# MD029A_DRV8300.net
KiCad netlist of a schematic drawn in Altium Designer
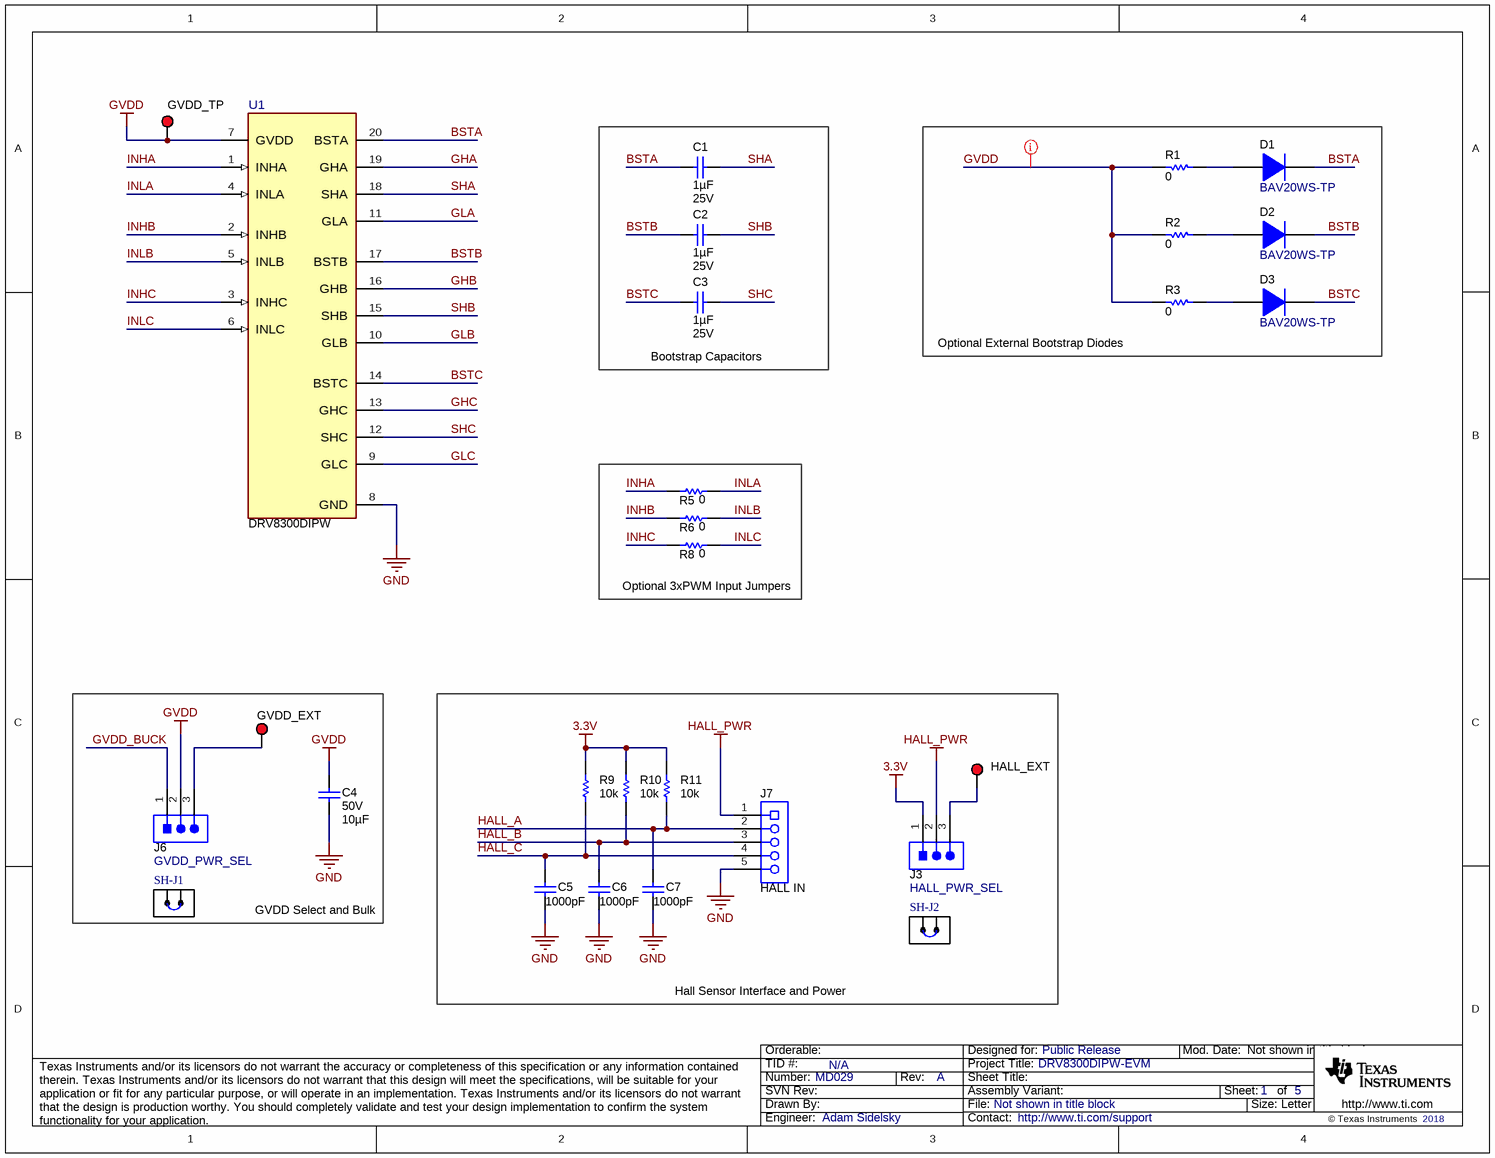
[diagram p0: MD029A_DRV8300.SchDoc]

(export (version "E")
  (design (tool "Eeschema 10.0.6"))
  (components
    (comp (ref "C1")
      (value "CL21B105KAFNNNE")
      (footprint "0805L")
      (description "CAP, CERM, 1 µF, 25 V,+/- 10%, X7R, 0805")
      (fields
        (field (name "MANUFACTURER") "Samsung Electro-Mechanics")
        (field (name "CAP_F") "1µF")
        (field (name "VDC_V") "25V")
      )
      (libsource (lib "Altium Vault - TI") (part "Capacitor"))
    )
    (comp (ref "C2")
      (value "CL21B105KAFNNNE")
      (footprint "0805L")
      (description "CAP, CERM, 1 µF, 25 V,+/- 10%, X7R, 0805")
      (fields
        (field (name "MANUFACTURER") "Samsung Electro-Mechanics")
        (field (name "CAP_F") "1µF")
        (field (name "VDC_V") "25V")
      )
      (libsource (lib "Altium Vault - TI") (part "Capacitor"))
    )
    (comp (ref "C3")
      (value "CL21B105KAFNNNE")
      (footprint "0805L")
      (description "CAP, CERM, 1 µF, 25 V,+/- 10%, X7R, 0805")
      (fields
        (field (name "MANUFACTURER") "Samsung Electro-Mechanics")
        (field (name "CAP_F") "1µF")
        (field (name "VDC_V") "25V")
      )
      (libsource (lib "Altium Vault - TI") (part "Capacitor"))
    )
    (comp (ref "C4")
      (value "CL32B106KBJNNWE")
      (footprint "1210_270L")
      (description "CAP, CERM, 10 µF, 50 V,+/- 10%, X7R, 1210")
      (fields
        (field (name "MANUFACTURER") "Samsung Electro-Mechanics")
        (field (name "VDC_V") "50V")
        (field (name "VALUEDISPLAYED") "10µF")
      )
      (libsource (lib "Altium Vault - TI") (part "Capacitor"))
    )
    (comp (ref "C5")
      (value "885012206034")
      (footprint "0603L")
      (description "CAP, CERM, 1000 pF, 16 V, +/- 10%, X7R, 0603")
      (fields
        (field (name "MANUFACTURER") "Wurth Elektronik")
        (field (name "VALUEDISPLAYED") "1000pF")
        (field (name "PUBLISHER") "Texas Instruments")
      )
      (libsource (lib "Altium Vault - TI") (part "CMP-0006826-4"))
    )
    (comp (ref "C6")
      (value "885012206034")
      (footprint "0603L")
      (description "CAP, CERM, 1000 pF, 16 V, +/- 10%, X7R, 0603")
      (fields
        (field (name "MANUFACTURER") "Wurth Elektronik")
        (field (name "VALUEDISPLAYED") "1000pF")
        (field (name "PUBLISHER") "Texas Instruments")
      )
      (libsource (lib "Altium Vault - TI") (part "CMP-0006826-4"))
    )
    (comp (ref "C7")
      (value "885012206034")
      (footprint "0603L")
      (description "CAP, CERM, 1000 pF, 16 V, +/- 10%, X7R, 0603")
      (fields
        (field (name "MANUFACTURER") "Wurth Elektronik")
        (field (name "VALUEDISPLAYED") "1000pF")
        (field (name "PUBLISHER") "Texas Instruments")
      )
      (libsource (lib "Altium Vault - TI") (part "CMP-0006826-4"))
    )
    (comp (ref "D1")
      (value "BAV20WS-TP")
      (footprint "SOD-323")
      (description "Diode, P-N, 150 V, 0.2 A, SOD-323")
      (fields (field (name "MANUFACTURER") "Micro Commercial Components"))
      (libsource (lib "Altium Vault - TI") (part "DIODE"))
    )
    (comp (ref "D2")
      (value "BAV20WS-TP")
      (footprint "SOD-323")
      (description "Diode, P-N, 150 V, 0.2 A, SOD-323")
      (fields (field (name "MANUFACTURER") "Micro Commercial Components"))
      (libsource (lib "Altium Vault - TI") (part "DIODE"))
    )
    (comp (ref "D3")
      (value "BAV20WS-TP")
      (footprint "SOD-323")
      (description "Diode, P-N, 150 V, 0.2 A, SOD-323")
      (fields (field (name "MANUFACTURER") "Micro Commercial Components"))
      (libsource (lib "Altium Vault - TI") (part "DIODE"))
    )
    (comp (ref "GVDD_EXT")
      (value "~")
      (footprint "Keystone5000")
      (description "Test Point, Miniature, Red, TH")
      (fields
        (field (name "PARTNUMBER") "5000")
        (field (name "MANUFACTURER") "Keystone")
        (field (name "PUBLISHER") "Texas Instruments")
      )
      (libsource (lib "Altium Vault - TI") (part "CMP-0055137-1"))
    )
    (comp (ref "GVDD_TP")
      (value "~")
      (footprint "Keystone5000")
      (description "Test Point, Miniature, Red, TH")
      (fields
        (field (name "PARTNUMBER") "5000")
        (field (name "MANUFACTURER") "Keystone")
        (field (name "PUBLISHER") "Texas Instruments")
      )
      (libsource (lib "Altium Vault - TI") (part "CMP-0055137-1"))
    )
    (comp (ref "HALL_EXT")
      (value "~")
      (footprint "Keystone5000")
      (description "Test Point, Miniature, Red, TH")
      (fields
        (field (name "PARTNUMBER") "5000")
        (field (name "MANUFACTURER") "Keystone")
        (field (name "PUBLISHER") "Texas Instruments")
      )
      (libsource (lib "Altium Vault - TI") (part "CMP-0055137-1"))
    )
    (comp (ref "J3")
      (value "HALL_PWR_SEL")
      (footprint "WURTH_61300311121")
      (description "Header, 2.54 mm, 3x1, Gold, TH")
      (fields (field (name "MANUFACTURER") "Wurth Elektronik") (field (name "PARTNUMBER") "61300311121"))
      (libsource (lib "Altium Vault - TI") (part "Header_3x1"))
    )
    (comp (ref "J6")
      (value "GVDD_PWR_SEL")
      (footprint "WURTH_61300311121")
      (description "Header, 2.54 mm, 3x1, Gold, TH")
      (fields (field (name "MANUFACTURER") "Wurth Elektronik") (field (name "PARTNUMBER") "61300311121"))
      (libsource (lib "Altium Vault - TI") (part "Header_3x1"))
    )
    (comp (ref "J7")
      (value "HALL IN")
      (footprint "Phoenix_1792892")
      (description "Terminal Block, 5mm, 5x1, R/A, TH")
      (fields
        (field (name "MANUFACTURER") "Phoenix Contact")
        (field (name "PARTNUMBER") "1792892")
        (field (name "PUBLISHER") "Texas Instruments")
      )
      (libsource (lib "Altium Vault - TI") (part "CMP-0055532-1"))
    )
    (comp (ref "R1")
      (value "CRCW08050000Z0EAHP")
      (footprint "0805L")
      (description "RES, 0, 5%, 0.333 W, AEC-Q200 Grade 0, 0805")
      (fields (field (name "MANUFACTURER") "Vishay-Dale") (field (name "VALUEDISPLAYED") "0"))
      (libsource (lib "Altium Vault - TI") (part "Resistor"))
    )
    (comp (ref "R2")
      (value "CRCW08050000Z0EAHP")
      (footprint "0805L")
      (description "RES, 0, 5%, 0.333 W, AEC-Q200 Grade 0, 0805")
      (fields (field (name "MANUFACTURER") "Vishay-Dale") (field (name "VALUEDISPLAYED") "0"))
      (libsource (lib "Altium Vault - TI") (part "Resistor"))
    )
    (comp (ref "R3")
      (value "CRCW08050000Z0EAHP")
      (footprint "0805L")
      (description "RES, 0, 5%, 0.333 W, AEC-Q200 Grade 0, 0805")
      (fields (field (name "MANUFACTURER") "Vishay-Dale") (field (name "VALUEDISPLAYED") "0"))
      (libsource (lib "Altium Vault - TI") (part "Resistor"))
    )
    (comp (ref "R5")
      (value "0")
      (footprint "0603L")
      (description "RES, 0, 5%, 0.1 W, AEC-Q200 Grade 0, 0603")
      (fields (field (name "PARTNUMBER") "CRCW06030000Z0EA") (field (name "MANUFACTURER") "Vishay-Dale"))
      (libsource (lib "Altium Vault - TI") (part "Resistor"))
    )
    (comp (ref "R6")
      (value "0")
      (footprint "0603L")
      (description "RES, 0, 5%, 0.1 W, AEC-Q200 Grade 0, 0603")
      (fields (field (name "PARTNUMBER") "CRCW06030000Z0EA") (field (name "MANUFACTURER") "Vishay-Dale"))
      (libsource (lib "Altium Vault - TI") (part "Resistor"))
    )
    (comp (ref "R8")
      (value "0")
      (footprint "0603L")
      (description "RES, 0, 5%, 0.1 W, AEC-Q200 Grade 0, 0603")
      (fields (field (name "PARTNUMBER") "CRCW06030000Z0EA") (field (name "MANUFACTURER") "Vishay-Dale"))
      (libsource (lib "Altium Vault - TI") (part "Resistor"))
    )
    (comp (ref "R9")
      (value "10k")
      (footprint "0603L")
      (description "RES, 10 k, 5%, 0.1 W, AEC-Q200 Grade 0, 0603")
      (fields (field (name "PARTNUMBER") "CRCW060310K0JNEA") (field (name "MANUFACTURER") "Vishay-Dale"))
      (libsource (lib "Altium Vault - TI") (part "Resistor"))
    )
    (comp (ref "R10")
      (value "10k")
      (footprint "0603L")
      (description "RES, 10 k, 5%, 0.1 W, AEC-Q200 Grade 0, 0603")
      (fields (field (name "PARTNUMBER") "CRCW060310K0JNEA") (field (name "MANUFACTURER") "Vishay-Dale"))
      (libsource (lib "Altium Vault - TI") (part "Resistor"))
    )
    (comp (ref "R11")
      (value "10k")
      (footprint "0603L")
      (description "RES, 10 k, 5%, 0.1 W, AEC-Q200 Grade 0, 0603")
      (fields (field (name "PARTNUMBER") "CRCW060310K0JNEA") (field (name "MANUFACTURER") "Vishay-Dale"))
      (libsource (lib "Altium Vault - TI") (part "Resistor"))
    )
    (comp (ref "SH-J1")
      (value "SNT-100-BK-G")
      (footprint "SNT-100-BK-G")
      (description "Shunt, 100mil, Gold plated, Black")
      (fields (field (name "ALTERNATE PARTNUMBER") "969102-0000-DA") (field (name "MANUFACTURER") "Samtec"))
      (libsource (lib "Altium Vault - TI") (part "Shunt"))
    )
    (comp (ref "SH-J2")
      (value "SNT-100-BK-G")
      (footprint "SNT-100-BK-G")
      (description "Shunt, 100mil, Gold plated, Black")
      (fields (field (name "ALTERNATE PARTNUMBER") "969102-0000-DA") (field (name "MANUFACTURER") "Samtec"))
      (libsource (lib "Altium Vault - TI") (part "Shunt"))
    )
    (comp (ref "U1")
      (value "DRV8300DIPW")
      (footprint "PW0020A-MFG")
      (description "Three-Phase BLDC Gate Driver")
      (fields (field (name "PARTNUMBER") "DRV8300DIPW") (field (name "MANUFACTURER") "Texas Instruments"))
      (libsource (lib "Altium Vault - TI") (part "SYM-DRV8300DIPW"))
    )
  )
  (nets
    (net (code "1") (name "/BSTA") (class "Default")
      (node (ref "C1") (pin "2") (pinfunction "2_2") (pintype "passive"))
      (node (ref "D1") (pin "1") (pinfunction "K_1") (pintype "passive"))
      (node (ref "U1") (pin "20") (pinfunction "BSTA_20") (pintype "passive"))
    )
    (net (code "2") (name "/BSTB") (class "Default")
      (node (ref "C2") (pin "2") (pinfunction "2_2") (pintype "passive"))
      (node (ref "D2") (pin "1") (pinfunction "K_1") (pintype "passive"))
      (node (ref "U1") (pin "17") (pinfunction "BSTB_17") (pintype "passive"))
    )
    (net (code "3") (name "/BSTC") (class "Default")
      (node (ref "C3") (pin "2") (pinfunction "2_2") (pintype "passive"))
      (node (ref "D3") (pin "1") (pinfunction "K_1") (pintype "passive"))
      (node (ref "U1") (pin "14") (pinfunction "BSTC_14") (pintype "passive"))
    )
    (net (code "4") (name "/GHA") (class "Default")
      (node (ref "U1") (pin "19") (pinfunction "GHA_19") (pintype "passive"))
    )
    (net (code "5") (name "/GHB") (class "Default")
      (node (ref "U1") (pin "16") (pinfunction "GHB_16") (pintype "passive"))
    )
    (net (code "6") (name "/GHC") (class "Default")
      (node (ref "U1") (pin "13") (pinfunction "GHC_13") (pintype "passive"))
    )
    (net (code "7") (name "/GLA") (class "Default")
      (node (ref "U1") (pin "11") (pinfunction "GLA_11") (pintype "passive"))
    )
    (net (code "8") (name "/GLB") (class "Default")
      (node (ref "U1") (pin "10") (pinfunction "GLB_10") (pintype "passive"))
    )
    (net (code "9") (name "/GLC") (class "Default")
      (node (ref "U1") (pin "9") (pinfunction "GLC_9") (pintype "passive"))
    )
    (net (code "10") (name "/GVDD_BUCK") (class "Default")
      (node (ref "J6") (pin "1") (pinfunction "1_1") (pintype "passive"))
    )
    (net (code "11") (name "/HALL_A") (class "Default")
      (node (ref "C7") (pin "1") (pinfunction "1_1") (pintype "passive"))
      (node (ref "J7") (pin "2") (pinfunction "2_2") (pintype "passive"))
      (node (ref "R11") (pin "2") (pinfunction "2_2") (pintype "passive"))
    )
    (net (code "12") (name "/HALL_B") (class "Default")
      (node (ref "C6") (pin "1") (pinfunction "1_1") (pintype "passive"))
      (node (ref "J7") (pin "3") (pinfunction "3_3") (pintype "passive"))
      (node (ref "R10") (pin "2") (pinfunction "2_2") (pintype "passive"))
    )
    (net (code "13") (name "/HALL_C") (class "Default")
      (node (ref "C5") (pin "1") (pinfunction "1_1") (pintype "passive"))
      (node (ref "J7") (pin "4") (pinfunction "4_4") (pintype "passive"))
      (node (ref "R9") (pin "2") (pinfunction "2_2") (pintype "passive"))
    )
    (net (code "14") (name "/INHA") (class "Default")
      (node (ref "R5") (pin "2") (pinfunction "2_2") (pintype "passive"))
      (node (ref "U1") (pin "1") (pinfunction "INHA_1") (pintype "input"))
    )
    (net (code "15") (name "/INHB") (class "Default")
      (node (ref "R6") (pin "2") (pinfunction "2_2") (pintype "passive"))
      (node (ref "U1") (pin "2") (pinfunction "INHB_2") (pintype "input"))
    )
    (net (code "16") (name "/INHC") (class "Default")
      (node (ref "R8") (pin "2") (pinfunction "2_2") (pintype "passive"))
      (node (ref "U1") (pin "3") (pinfunction "INHC_3") (pintype "input"))
    )
    (net (code "17") (name "/INLA") (class "Default")
      (node (ref "R5") (pin "1") (pinfunction "1_1") (pintype "passive"))
      (node (ref "U1") (pin "4") (pinfunction "INLA_4") (pintype "input"))
    )
    (net (code "18") (name "/INLB") (class "Default")
      (node (ref "R6") (pin "1") (pinfunction "1_1") (pintype "passive"))
      (node (ref "U1") (pin "5") (pinfunction "INLB_5") (pintype "input"))
    )
    (net (code "19") (name "/INLC") (class "Default")
      (node (ref "R8") (pin "1") (pinfunction "1_1") (pintype "passive"))
      (node (ref "U1") (pin "6") (pinfunction "INLC_6") (pintype "input"))
    )
    (net (code "20") (name "/SHA") (class "Default")
      (node (ref "C1") (pin "1") (pinfunction "1_1") (pintype "passive"))
      (node (ref "U1") (pin "18") (pinfunction "SHA_18") (pintype "passive"))
    )
    (net (code "21") (name "/SHB") (class "Default")
      (node (ref "C2") (pin "1") (pinfunction "1_1") (pintype "passive"))
      (node (ref "U1") (pin "15") (pinfunction "SHB_15") (pintype "passive"))
    )
    (net (code "22") (name "/SHC") (class "Default")
      (node (ref "C3") (pin "1") (pinfunction "1_1") (pintype "passive"))
      (node (ref "U1") (pin "12") (pinfunction "SHC_12") (pintype "passive"))
    )
    (net (code "23") (name "3.3V") (class "Default")
      (node (ref "J3") (pin "1") (pinfunction "1_1") (pintype "passive"))
      (node (ref "R10") (pin "1") (pinfunction "1_1") (pintype "passive"))
      (node (ref "R11") (pin "1") (pinfunction "1_1") (pintype "passive"))
      (node (ref "R9") (pin "1") (pinfunction "1_1") (pintype "passive"))
    )
    (net (code "24") (name "GND") (class "Default")
      (node (ref "C4") (pin "2") (pinfunction "2_2") (pintype "passive"))
      (node (ref "C5") (pin "2") (pinfunction "2_2") (pintype "passive"))
      (node (ref "C6") (pin "2") (pinfunction "2_2") (pintype "passive"))
      (node (ref "C7") (pin "2") (pinfunction "2_2") (pintype "passive"))
      (node (ref "J7") (pin "5") (pinfunction "5_5") (pintype "passive"))
      (node (ref "U1") (pin "8") (pinfunction "GND_8") (pintype "power_in"))
    )
    (net (code "25") (name "GVDD") (class "Default")
      (node (ref "C4") (pin "1") (pinfunction "1_1") (pintype "passive"))
      (node (ref "GVDD_TP") (pin "1") (pintype "passive"))
      (node (ref "J6") (pin "2") (pinfunction "2_2") (pintype "passive"))
      (node (ref "R1") (pin "2") (pinfunction "2_2") (pintype "passive"))
      (node (ref "R2") (pin "2") (pinfunction "2_2") (pintype "passive"))
      (node (ref "R3") (pin "2") (pinfunction "2_2") (pintype "passive"))
      (node (ref "U1") (pin "7") (pinfunction "GVDD_7") (pintype "power_in"))
    )
    (net (code "26") (name "HALL_PWR") (class "Default")
      (node (ref "J3") (pin "2") (pinfunction "2_2") (pintype "passive"))
      (node (ref "J7") (pin "1") (pinfunction "1_1") (pintype "passive"))
    )
    (net (code "27") (name "Net-(D1-A)") (class "Default")
      (node (ref "D1") (pin "2") (pinfunction "A_2") (pintype "passive"))
      (node (ref "R1") (pin "1") (pinfunction "1_1") (pintype "passive"))
    )
    (net (code "28") (name "Net-(D2-A)") (class "Default")
      (node (ref "D2") (pin "2") (pinfunction "A_2") (pintype "passive"))
      (node (ref "R2") (pin "1") (pinfunction "1_1") (pintype "passive"))
    )
    (net (code "29") (name "Net-(D3-A)") (class "Default")
      (node (ref "D3") (pin "2") (pinfunction "A_2") (pintype "passive"))
      (node (ref "R3") (pin "1") (pinfunction "1_1") (pintype "passive"))
    )
    (net (code "30") (name "Net-(GVDD_EXT-Pad1)") (class "Default")
      (node (ref "GVDD_EXT") (pin "1") (pintype "passive"))
      (node (ref "J6") (pin "3") (pinfunction "3_3") (pintype "passive"))
    )
    (net (code "31") (name "Net-(HALL_EXT-Pad1)") (class "Default")
      (node (ref "HALL_EXT") (pin "1") (pintype "passive"))
      (node (ref "J3") (pin "3") (pinfunction "3_3") (pintype "passive"))
    )
  )
)
